# mainboard_mcu_v1_2.net
KiCad netlist of a schematic drawn in Altium Designer
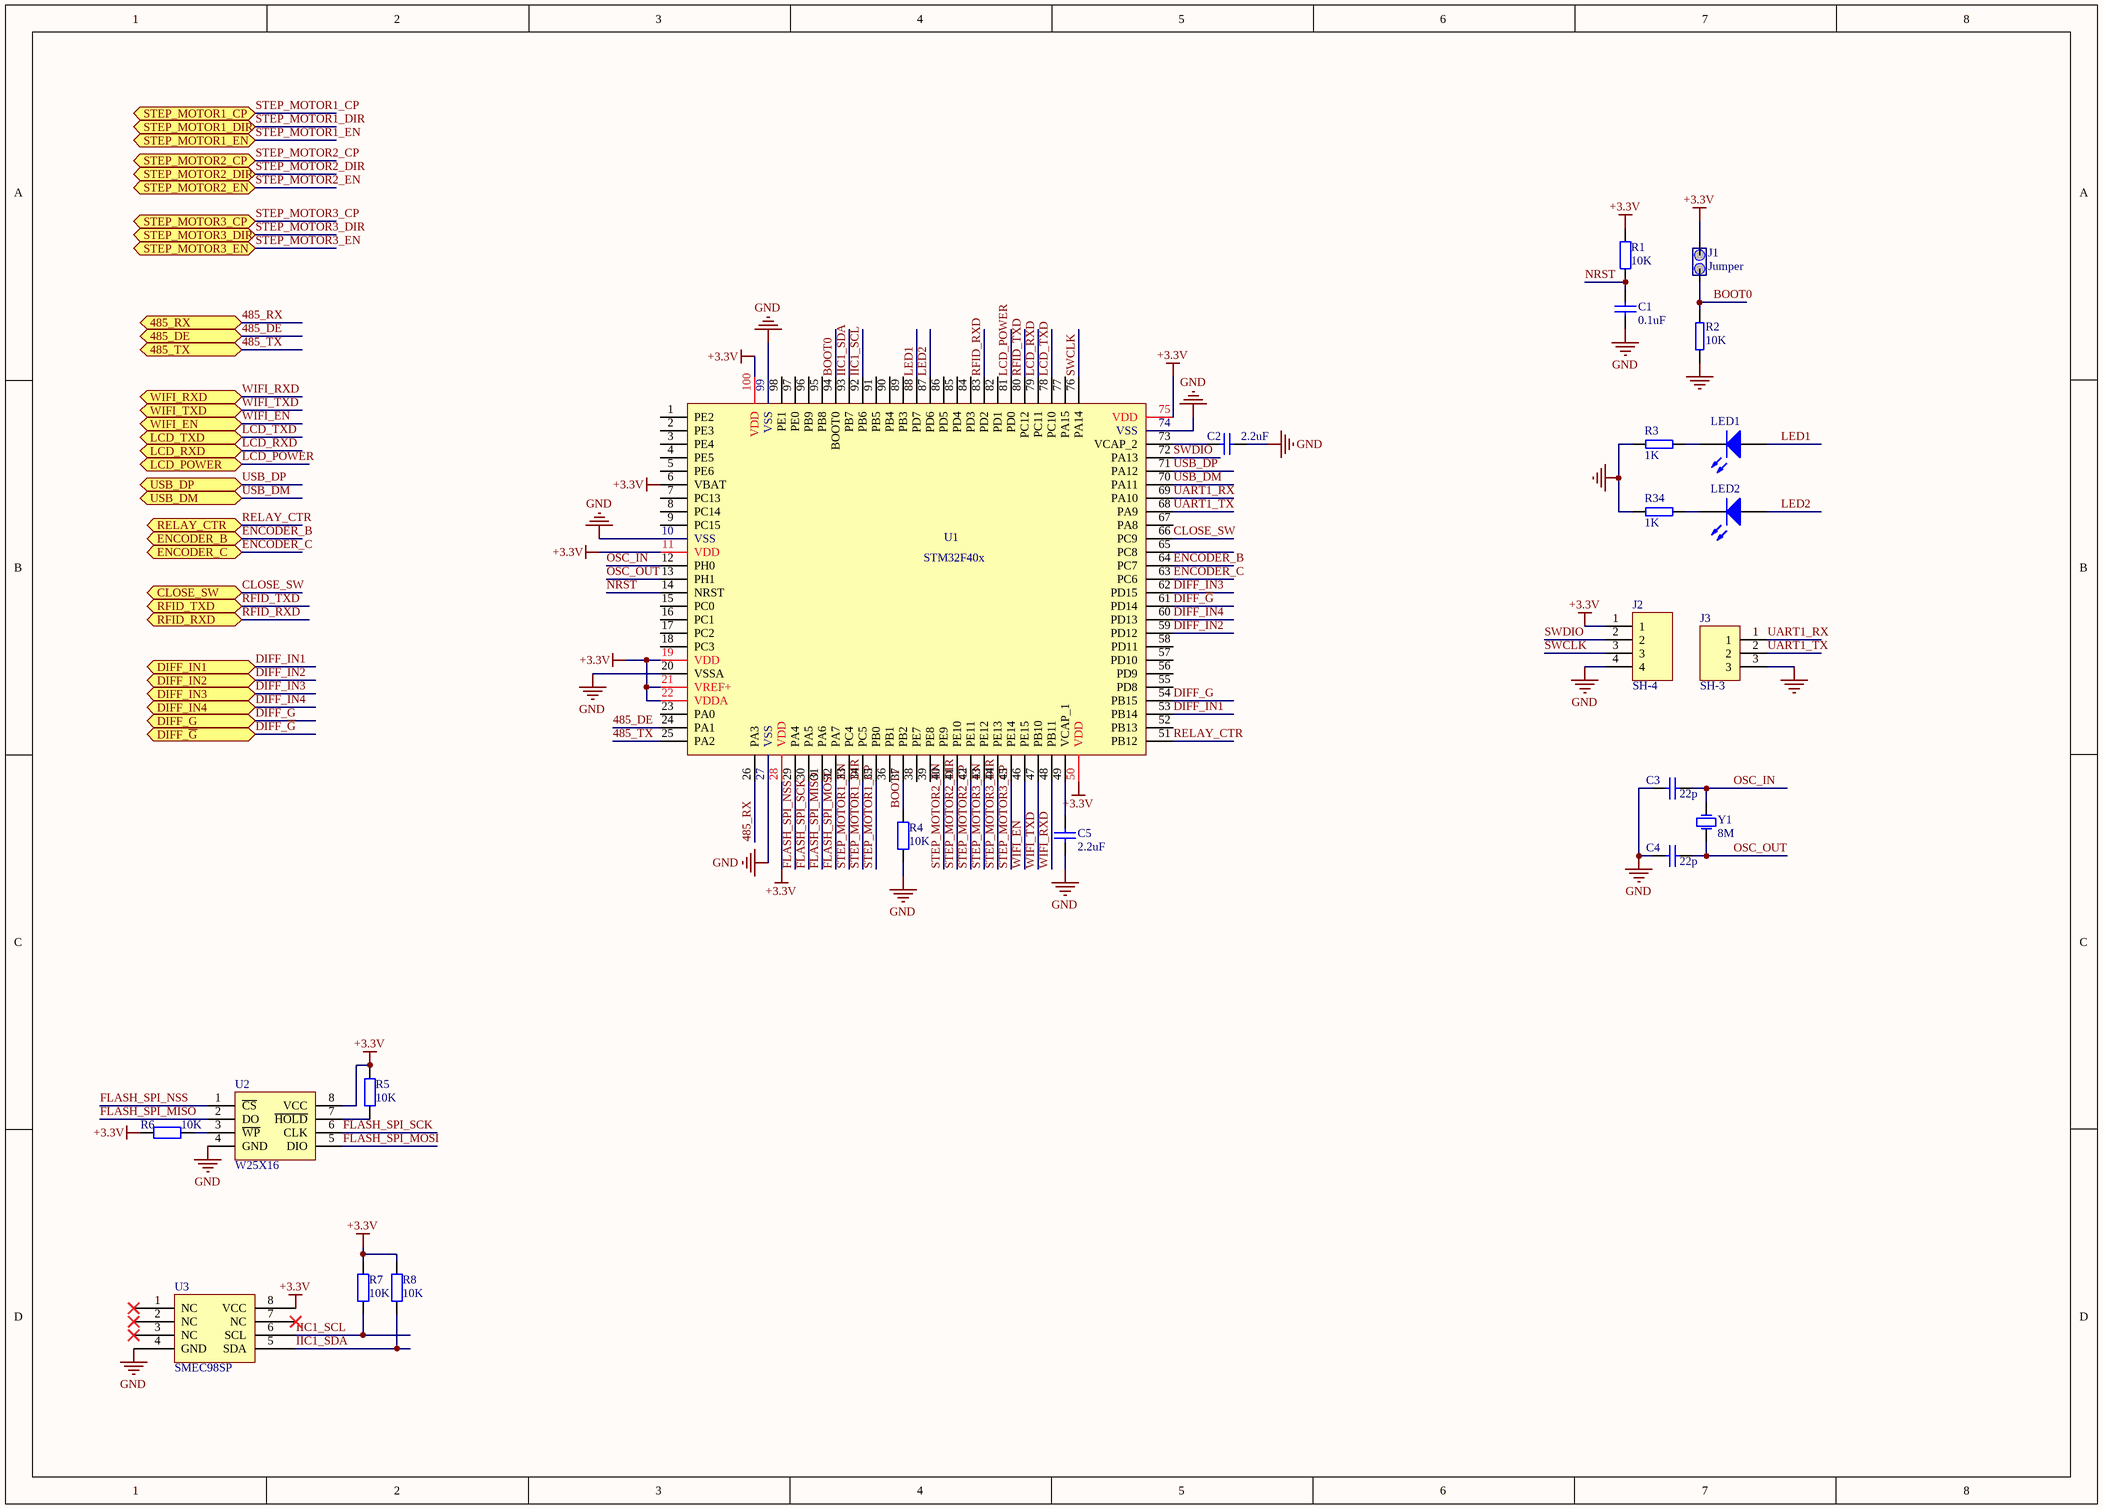
[diagram p0: mainboard_mcu.v1.2.SchDoc]

(export (version "E")
  (design (tool "Eeschema 10.0.6"))
  (components
    (comp (ref "C1")
      (value "0.1uF")
      (footprint "0805")
      (description "Capacitor")
      (fields (field (name "PUBLISHER") "Altium Limited"))
      (libsource (lib "TIAN's Schlib") (part "Cap"))
    )
    (comp (ref "C2")
      (value "2.2uF")
      (footprint "0805")
      (description "Capacitor")
      (fields (field (name "PUBLISHER") "Altium Limited"))
      (libsource (lib "TIAN's Schlib") (part "Cap"))
    )
    (comp (ref "C3")
      (value "22p")
      (footprint "0805")
      (description "Capacitor")
      (fields (field (name "PUBLISHER") "Altium Limited"))
      (libsource (lib "TIAN's Schlib") (part "Cap"))
    )
    (comp (ref "C4")
      (value "22p")
      (footprint "0805")
      (description "Capacitor")
      (fields (field (name "PUBLISHER") "Altium Limited"))
      (libsource (lib "TIAN's Schlib") (part "Cap"))
    )
    (comp (ref "C5")
      (value "2.2uF")
      (footprint "0805")
      (description "Capacitor")
      (fields (field (name "PUBLISHER") "Altium Limited"))
      (libsource (lib "TIAN's Schlib") (part "Cap"))
    )
    (comp (ref "J1") (value "Jumper") (footprint "J254-2") (libsource (lib "Connector") (part "Jumper")))
    (comp (ref "J2") (value "SH-4") (footprint "J254-4") (libsource (lib "Connector") (part "SH-4")))
    (comp (ref "J3") (value "SH-3") (footprint "J2.54-3") (libsource (lib "Connector") (part "SH-3")))
    (comp (ref "LED1")
      (value "GREEN")
      (footprint "LED")
      (description "Typical RED, GREEN, YELLOW, AMBER GaAs LED")
      (fields (field (name "PUBLISHER") "Altium Limited"))
      (libsource (lib "Miscellaneous Devices") (part "LED2"))
    )
    (comp (ref "LED2")
      (value "GREEN")
      (footprint "LED")
      (description "Typical RED, GREEN, YELLOW, AMBER GaAs LED")
      (fields (field (name "PUBLISHER") "Altium Limited"))
      (libsource (lib "Miscellaneous Devices") (part "LED2"))
    )
    (comp (ref "R1")
      (value "10K")
      (footprint "0805")
      (description "Resistor")
      (fields (field (name "PUBLISHER") "Altium Limited"))
      (libsource (lib "") (part "Res2_1"))
    )
    (comp (ref "R2")
      (value "10K")
      (footprint "0805")
      (description "电阻")
      (libsource (lib "Component") (part "RES"))
    )
    (comp (ref "R3")
      (value "1K")
      (footprint "0805")
      (description "电阻")
      (libsource (lib "Component") (part "RES"))
    )
    (comp (ref "R4")
      (value "10K")
      (footprint "0805")
      (description "Resistor")
      (fields (field (name "PUBLISHER") "Altium Limited"))
      (libsource (lib "TIAN's Schlib") (part "Res2"))
    )
    (comp (ref "R5")
      (value "10K")
      (footprint "0805")
      (description "Resistor")
      (fields (field (name "PUBLISHER") "Altium Limited"))
      (libsource (lib "TIAN's Schlib") (part "Res2"))
    )
    (comp (ref "R6")
      (value "10K")
      (footprint "0805")
      (description "Resistor")
      (fields (field (name "PUBLISHER") "Altium Limited"))
      (libsource (lib "") (part "Res2_2"))
    )
    (comp (ref "R7")
      (value "10K")
      (footprint "0805")
      (description "Resistor")
      (fields (field (name "PUBLISHER") "Altium Limited"))
      (libsource (lib "") (part "Res2_1"))
    )
    (comp (ref "R8")
      (value "10K")
      (footprint "0805")
      (description "Resistor")
      (fields (field (name "PUBLISHER") "Altium Limited"))
      (libsource (lib "") (part "Res2_1"))
    )
    (comp (ref "R34")
      (value "1K")
      (footprint "0805")
      (description "电阻")
      (libsource (lib "Component") (part "RES"))
    )
    (comp (ref "U1") (value "STM32F40x") (footprint "TQFP100") (libsource (lib "Chip") (part "STM32F40x")))
    (comp (ref "U2") (value "W25X16") (footprint "SOP8") (libsource (lib "Chip") (part "W25X16")))
    (comp (ref "U3") (value "SMEC98SP") (footprint "SO-8") (libsource (lib "Chip") (part "SMEC98SP")))
    (comp (ref "Y1")
      (value "8M")
      (footprint "XTAL")
      (description "Crystal Oscillator")
      (fields (field (name "PUBLISHER") "Altium Limited"))
      (libsource (lib "TIAN's Schlib") (part "X-32.768"))
    )
  )
  (nets
    (net (code "1") (name "+3.3V") (class "Default")
      (node (ref "J1") (pin "2") (pinfunction "2_2") (pintype "passive"))
      (node (ref "J2") (pin "1") (pinfunction "1_1") (pintype "passive"))
      (node (ref "R1") (pin "2") (pinfunction "2_2") (pintype "passive"))
      (node (ref "R5") (pin "1") (pinfunction "1_1") (pintype "passive"))
      (node (ref "R6") (pin "2") (pinfunction "2_2") (pintype "passive"))
      (node (ref "R7") (pin "2") (pinfunction "2_2") (pintype "passive"))
      (node (ref "R8") (pin "2") (pinfunction "2_2") (pintype "passive"))
      (node (ref "U1") (pin "100") (pinfunction "VDD_100") (pintype "passive"))
      (node (ref "U1") (pin "11") (pinfunction "VDD_11") (pintype "passive"))
      (node (ref "U1") (pin "19") (pinfunction "VDD_19") (pintype "passive"))
      (node (ref "U1") (pin "21") (pinfunction "VREF+_21") (pintype "passive"))
      (node (ref "U1") (pin "22") (pinfunction "VDDA_22") (pintype "passive"))
      (node (ref "U1") (pin "28") (pinfunction "VDD_28") (pintype "passive"))
      (node (ref "U1") (pin "50") (pinfunction "VDD_50") (pintype "passive"))
      (node (ref "U1") (pin "6") (pinfunction "VBAT_6") (pintype "passive"))
      (node (ref "U1") (pin "75") (pinfunction "VDD_75") (pintype "passive"))
      (node (ref "U2") (pin "8") (pinfunction "VCC_8") (pintype "passive"))
      (node (ref "U3") (pin "8") (pinfunction "VCC_8") (pintype "passive"))
    )
    (net (code "2") (name "/485_DE") (class "Default")
      (node (ref "U1") (pin "24") (pinfunction "PA1_24") (pintype "passive"))
    )
    (net (code "3") (name "/485_RX") (class "Default")
      (node (ref "U1") (pin "26") (pinfunction "PA3_26") (pintype "passive"))
    )
    (net (code "4") (name "/485_TX") (class "Default")
      (node (ref "U1") (pin "25") (pinfunction "PA2_25") (pintype "passive"))
    )
    (net (code "5") (name "/BOOT0") (class "Default")
      (node (ref "J1") (pin "1") (pinfunction "1_1") (pintype "passive"))
      (node (ref "R2") (pin "1") (pinfunction "1_1") (pintype "passive"))
      (node (ref "U1") (pin "94") (pinfunction "BOOT0_94") (pintype "passive"))
    )
    (net (code "6") (name "/BOOT1") (class "Default")
      (node (ref "R4") (pin "1") (pinfunction "1_1") (pintype "passive"))
      (node (ref "U1") (pin "37") (pinfunction "PB2_37") (pintype "passive"))
    )
    (net (code "7") (name "/CLOSE_SW") (class "Default")
      (node (ref "U1") (pin "66") (pinfunction "PC9_66") (pintype "passive"))
    )
    (net (code "8") (name "/DIFF_G") (class "Default")
      (node (ref "U1") (pin "54") (pinfunction "PB15_54") (pintype "passive"))
    )
    (net (code "9") (name "/DIFF_IN1") (class "Default")
      (node (ref "U1") (pin "53") (pinfunction "PB14_53") (pintype "passive"))
    )
    (net (code "10") (name "/DIFF_IN2") (class "Default")
      (node (ref "U1") (pin "59") (pinfunction "PD12_59") (pintype "passive"))
    )
    (net (code "11") (name "/DIFF_IN3") (class "Default")
      (node (ref "U1") (pin "62") (pinfunction "PD15_62") (pintype "passive"))
    )
    (net (code "12") (name "/DIFF_IN4") (class "Default")
      (node (ref "U1") (pin "60") (pinfunction "PD13_60") (pintype "passive"))
    )
    (net (code "13") (name "/DIFF_~{G}") (class "Default")
      (node (ref "U1") (pin "61") (pinfunction "PD14_61") (pintype "passive"))
    )
    (net (code "14") (name "/ENCODER_B") (class "Default")
      (node (ref "U1") (pin "64") (pinfunction "PC7_64") (pintype "passive"))
    )
    (net (code "15") (name "/ENCODER_C") (class "Default")
      (node (ref "U1") (pin "63") (pinfunction "PC6_63") (pintype "passive"))
    )
    (net (code "16") (name "/FLASH_SPI_MISO") (class "Default")
      (node (ref "U1") (pin "31") (pinfunction "PA6_31") (pintype "passive"))
      (node (ref "U2") (pin "2") (pinfunction "DO_2") (pintype "passive"))
    )
    (net (code "17") (name "/FLASH_SPI_MOSI") (class "Default")
      (node (ref "U1") (pin "32") (pinfunction "PA7_32") (pintype "passive"))
      (node (ref "U2") (pin "5") (pinfunction "DIO_5") (pintype "passive"))
    )
    (net (code "18") (name "/FLASH_SPI_NSS") (class "Default")
      (node (ref "U1") (pin "29") (pinfunction "PA4_29") (pintype "passive"))
      (node (ref "U2") (pin "1") (pinfunction "~{CS}_1") (pintype "passive"))
    )
    (net (code "19") (name "/FLASH_SPI_SCK") (class "Default")
      (node (ref "U1") (pin "30") (pinfunction "PA5_30") (pintype "passive"))
      (node (ref "U2") (pin "6") (pinfunction "CLK_6") (pintype "passive"))
    )
    (net (code "20") (name "/IIC1_SCL") (class "Default")
      (node (ref "R7") (pin "1") (pinfunction "1_1") (pintype "passive"))
      (node (ref "U1") (pin "92") (pinfunction "PB6_92") (pintype "passive"))
      (node (ref "U3") (pin "6") (pinfunction "SCL_6") (pintype "passive"))
    )
    (net (code "21") (name "/IIC1_SDA") (class "Default")
      (node (ref "R8") (pin "1") (pinfunction "1_1") (pintype "passive"))
      (node (ref "U1") (pin "93") (pinfunction "PB7_93") (pintype "passive"))
      (node (ref "U3") (pin "5") (pinfunction "SDA_5") (pintype "passive"))
    )
    (net (code "22") (name "/LCD_POWER") (class "Default")
      (node (ref "U1") (pin "81") (pinfunction "PD0_81") (pintype "passive"))
    )
    (net (code "23") (name "/LCD_RXD") (class "Default")
      (node (ref "U1") (pin "79") (pinfunction "PC11_79") (pintype "passive"))
    )
    (net (code "24") (name "/LCD_TXD") (class "Default")
      (node (ref "U1") (pin "78") (pinfunction "PC10_78") (pintype "passive"))
    )
    (net (code "25") (name "/LED1") (class "Default")
      (node (ref "LED1") (pin "1") (pinfunction "A_1") (pintype "passive"))
      (node (ref "U1") (pin "88") (pinfunction "PD7_88") (pintype "passive"))
    )
    (net (code "26") (name "/LED2") (class "Default")
      (node (ref "LED2") (pin "1") (pinfunction "A_1") (pintype "passive"))
      (node (ref "U1") (pin "87") (pinfunction "PD6_87") (pintype "passive"))
    )
    (net (code "27") (name "/NRST") (class "Default")
      (node (ref "C1") (pin "2") (pinfunction "2_2") (pintype "passive"))
      (node (ref "R1") (pin "1") (pinfunction "1_1") (pintype "passive"))
      (node (ref "U1") (pin "14") (pinfunction "NRST_14") (pintype "passive"))
    )
    (net (code "28") (name "/OSC_IN") (class "Default")
      (node (ref "C3") (pin "1") (pinfunction "1_1") (pintype "passive"))
      (node (ref "U1") (pin "12") (pinfunction "PH0_12") (pintype "passive"))
      (node (ref "Y1") (pin "2") (pinfunction "OSC2_2") (pintype "passive"))
    )
    (net (code "29") (name "/OSC_OUT") (class "Default")
      (node (ref "C4") (pin "1") (pinfunction "1_1") (pintype "passive"))
      (node (ref "U1") (pin "13") (pinfunction "PH1_13") (pintype "passive"))
      (node (ref "Y1") (pin "1") (pinfunction "OSC1_1") (pintype "passive"))
    )
    (net (code "30") (name "/RELAY_CTR") (class "Default")
      (node (ref "U1") (pin "51") (pinfunction "PB12_51") (pintype "passive"))
    )
    (net (code "31") (name "/RFID_RXD") (class "Default")
      (node (ref "U1") (pin "83") (pinfunction "PD2_83") (pintype "passive"))
    )
    (net (code "32") (name "/RFID_TXD") (class "Default")
      (node (ref "U1") (pin "80") (pinfunction "PC12_80") (pintype "passive"))
    )
    (net (code "33") (name "/STEP_MOTOR1_CP") (class "Default")
      (node (ref "U1") (pin "35") (pinfunction "PB0_35") (pintype "passive"))
    )
    (net (code "34") (name "/STEP_MOTOR1_DIR") (class "Default")
      (node (ref "U1") (pin "34") (pinfunction "PC5_34") (pintype "passive"))
    )
    (net (code "35") (name "/STEP_MOTOR1_EN") (class "Default")
      (node (ref "U1") (pin "33") (pinfunction "PC4_33") (pintype "passive"))
    )
    (net (code "36") (name "/STEP_MOTOR2_CP") (class "Default")
      (node (ref "U1") (pin "42") (pinfunction "PE11_42") (pintype "passive"))
    )
    (net (code "37") (name "/STEP_MOTOR2_DIR") (class "Default")
      (node (ref "U1") (pin "41") (pinfunction "PE10_41") (pintype "passive"))
    )
    (net (code "38") (name "/STEP_MOTOR2_EN") (class "Default")
      (node (ref "U1") (pin "40") (pinfunction "PE9_40") (pintype "passive"))
    )
    (net (code "39") (name "/STEP_MOTOR3_CP") (class "Default")
      (node (ref "U1") (pin "45") (pinfunction "PE14_45") (pintype "passive"))
    )
    (net (code "40") (name "/STEP_MOTOR3_DIR") (class "Default")
      (node (ref "U1") (pin "44") (pinfunction "PE13_44") (pintype "passive"))
    )
    (net (code "41") (name "/STEP_MOTOR3_EN") (class "Default")
      (node (ref "U1") (pin "43") (pinfunction "PE12_43") (pintype "passive"))
    )
    (net (code "42") (name "/SWCLK") (class "Default")
      (node (ref "J2") (pin "3") (pinfunction "3_3") (pintype "passive"))
      (node (ref "U1") (pin "76") (pinfunction "PA14_76") (pintype "passive"))
    )
    (net (code "43") (name "/SWDIO") (class "Default")
      (node (ref "J2") (pin "2") (pinfunction "2_2") (pintype "passive"))
      (node (ref "U1") (pin "72") (pinfunction "PA13_72") (pintype "passive"))
    )
    (net (code "44") (name "/UART1_RX") (class "Default")
      (node (ref "J3") (pin "1") (pinfunction "1_1") (pintype "passive"))
      (node (ref "U1") (pin "69") (pinfunction "PA10_69") (pintype "passive"))
    )
    (net (code "45") (name "/UART1_TX") (class "Default")
      (node (ref "J3") (pin "2") (pinfunction "2_2") (pintype "passive"))
      (node (ref "U1") (pin "68") (pinfunction "PA9_68") (pintype "passive"))
    )
    (net (code "46") (name "/USB_DM") (class "Default")
      (node (ref "U1") (pin "70") (pinfunction "PA11_70") (pintype "passive"))
    )
    (net (code "47") (name "/USB_DP") (class "Default")
      (node (ref "U1") (pin "71") (pinfunction "PA12_71") (pintype "passive"))
    )
    (net (code "48") (name "/WIFI_EN") (class "Default")
      (node (ref "U1") (pin "46") (pinfunction "PE15_46") (pintype "passive"))
    )
    (net (code "49") (name "/WIFI_RXD") (class "Default")
      (node (ref "U1") (pin "48") (pinfunction "PB11_48") (pintype "passive"))
    )
    (net (code "50") (name "/WIFI_TXD") (class "Default")
      (node (ref "U1") (pin "47") (pinfunction "PB10_47") (pintype "passive"))
    )
    (net (code "51") (name "GND") (class "Default")
      (node (ref "C1") (pin "1") (pinfunction "1_1") (pintype "passive"))
      (node (ref "C2") (pin "1") (pinfunction "1_1") (pintype "passive"))
      (node (ref "C3") (pin "2") (pinfunction "2_2") (pintype "passive"))
      (node (ref "C4") (pin "2") (pinfunction "2_2") (pintype "passive"))
      (node (ref "C5") (pin "2") (pinfunction "2_2") (pintype "passive"))
      (node (ref "J2") (pin "4") (pinfunction "4_4") (pintype "passive"))
      (node (ref "J3") (pin "3") (pinfunction "3_3") (pintype "passive"))
      (node (ref "R2") (pin "2") (pinfunction "2_2") (pintype "passive"))
      (node (ref "R3") (pin "2") (pinfunction "2_2") (pintype "passive"))
      (node (ref "R34") (pin "2") (pinfunction "2_2") (pintype "passive"))
      (node (ref "R4") (pin "2") (pinfunction "2_2") (pintype "passive"))
      (node (ref "U1") (pin "10") (pinfunction "VSS_10") (pintype "passive"))
      (node (ref "U1") (pin "20") (pinfunction "VSSA_20") (pintype "passive"))
      (node (ref "U1") (pin "27") (pinfunction "VSS_27") (pintype "passive"))
      (node (ref "U1") (pin "74") (pinfunction "VSS_74") (pintype "passive"))
      (node (ref "U1") (pin "99") (pinfunction "VSS_99") (pintype "passive"))
      (node (ref "U2") (pin "4") (pinfunction "GND_4") (pintype "passive"))
      (node (ref "U3") (pin "4") (pinfunction "GND_4") (pintype "passive"))
    )
    (net (code "52") (name "Net-(LED1-K)") (class "Default")
      (node (ref "LED1") (pin "2") (pinfunction "K_2") (pintype "passive"))
      (node (ref "R3") (pin "1") (pinfunction "1_1") (pintype "passive"))
    )
    (net (code "53") (name "Net-(LED2-K)") (class "Default")
      (node (ref "LED2") (pin "2") (pinfunction "K_2") (pintype "passive"))
      (node (ref "R34") (pin "1") (pinfunction "1_1") (pintype "passive"))
    )
    (net (code "54") (name "Net-(U1-VCAP_1)") (class "Default")
      (node (ref "C5") (pin "1") (pinfunction "1_1") (pintype "passive"))
      (node (ref "U1") (pin "49") (pinfunction "VCAP_1_49") (pintype "passive"))
    )
    (net (code "55") (name "Net-(U1-VCAP_2)") (class "Default")
      (node (ref "C2") (pin "2") (pinfunction "2_2") (pintype "passive"))
      (node (ref "U1") (pin "73") (pinfunction "VCAP_2_73") (pintype "passive"))
    )
    (net (code "56") (name "Net-(U2-~{HOLD})") (class "Default")
      (node (ref "R5") (pin "2") (pinfunction "2_2") (pintype "passive"))
      (node (ref "U2") (pin "7") (pinfunction "~{HOLD}_7") (pintype "passive"))
    )
    (net (code "57") (name "Net-(U2-~{WP})") (class "Default")
      (node (ref "R6") (pin "1") (pinfunction "1_1") (pintype "passive"))
      (node (ref "U2") (pin "3") (pinfunction "~{WP}_3") (pintype "passive"))
    )
    (net (code "58") (name "unconnected-(U1-PA0-Pad23)") (class "Default")
      (node (ref "U1") (pin "23") (pinfunction "PA0_23") (pintype "passive"))
    )
    (net (code "59") (name "unconnected-(U1-PA8-Pad67)") (class "Default")
      (node (ref "U1") (pin "67") (pinfunction "PA8_67") (pintype "passive"))
    )
    (net (code "60") (name "unconnected-(U1-PA15-Pad77)") (class "Default")
      (node (ref "U1") (pin "77") (pinfunction "PA15_77") (pintype "passive"))
    )
    (net (code "61") (name "unconnected-(U1-PB1-Pad36)") (class "Default")
      (node (ref "U1") (pin "36") (pinfunction "PB1_36") (pintype "passive"))
    )
    (net (code "62") (name "unconnected-(U1-PB3-Pad89)") (class "Default")
      (node (ref "U1") (pin "89") (pinfunction "PB3_89") (pintype "passive"))
    )
    (net (code "63") (name "unconnected-(U1-PB4-Pad90)") (class "Default")
      (node (ref "U1") (pin "90") (pinfunction "PB4_90") (pintype "passive"))
    )
    (net (code "64") (name "unconnected-(U1-PB5-Pad91)") (class "Default")
      (node (ref "U1") (pin "91") (pinfunction "PB5_91") (pintype "passive"))
    )
    (net (code "65") (name "unconnected-(U1-PB8-Pad95)") (class "Default")
      (node (ref "U1") (pin "95") (pinfunction "PB8_95") (pintype "passive"))
    )
    (net (code "66") (name "unconnected-(U1-PB9-Pad96)") (class "Default")
      (node (ref "U1") (pin "96") (pinfunction "PB9_96") (pintype "passive"))
    )
    (net (code "67") (name "unconnected-(U1-PB13-Pad52)") (class "Default")
      (node (ref "U1") (pin "52") (pinfunction "PB13_52") (pintype "passive"))
    )
    (net (code "68") (name "unconnected-(U1-PC0-Pad15)") (class "Default")
      (node (ref "U1") (pin "15") (pinfunction "PC0_15") (pintype "passive"))
    )
    (net (code "69") (name "unconnected-(U1-PC1-Pad16)") (class "Default")
      (node (ref "U1") (pin "16") (pinfunction "PC1_16") (pintype "passive"))
    )
    (net (code "70") (name "unconnected-(U1-PC2-Pad17)") (class "Default")
      (node (ref "U1") (pin "17") (pinfunction "PC2_17") (pintype "passive"))
    )
    (net (code "71") (name "unconnected-(U1-PC3-Pad18)") (class "Default")
      (node (ref "U1") (pin "18") (pinfunction "PC3_18") (pintype "passive"))
    )
    (net (code "72") (name "unconnected-(U1-PC8-Pad65)") (class "Default")
      (node (ref "U1") (pin "65") (pinfunction "PC8_65") (pintype "passive"))
    )
    (net (code "73") (name "unconnected-(U1-PC13-Pad7)") (class "Default")
      (node (ref "U1") (pin "7") (pinfunction "PC13_7") (pintype "passive"))
    )
    (net (code "74") (name "unconnected-(U1-PC14-Pad8)") (class "Default")
      (node (ref "U1") (pin "8") (pinfunction "PC14_8") (pintype "passive"))
    )
    (net (code "75") (name "unconnected-(U1-PC15-Pad9)") (class "Default")
      (node (ref "U1") (pin "9") (pinfunction "PC15_9") (pintype "passive"))
    )
    (net (code "76") (name "unconnected-(U1-PD1-Pad82)") (class "Default")
      (node (ref "U1") (pin "82") (pinfunction "PD1_82") (pintype "passive"))
    )
    (net (code "77") (name "unconnected-(U1-PD3-Pad84)") (class "Default")
      (node (ref "U1") (pin "84") (pinfunction "PD3_84") (pintype "passive"))
    )
    (net (code "78") (name "unconnected-(U1-PD4-Pad85)") (class "Default")
      (node (ref "U1") (pin "85") (pinfunction "PD4_85") (pintype "passive"))
    )
    (net (code "79") (name "unconnected-(U1-PD5-Pad86)") (class "Default")
      (node (ref "U1") (pin "86") (pinfunction "PD5_86") (pintype "passive"))
    )
    (net (code "80") (name "unconnected-(U1-PD8-Pad55)") (class "Default")
      (node (ref "U1") (pin "55") (pinfunction "PD8_55") (pintype "passive"))
    )
    (net (code "81") (name "unconnected-(U1-PD9-Pad56)") (class "Default")
      (node (ref "U1") (pin "56") (pinfunction "PD9_56") (pintype "passive"))
    )
    (net (code "82") (name "unconnected-(U1-PD10-Pad57)") (class "Default")
      (node (ref "U1") (pin "57") (pinfunction "PD10_57") (pintype "passive"))
    )
    (net (code "83") (name "unconnected-(U1-PD11-Pad58)") (class "Default")
      (node (ref "U1") (pin "58") (pinfunction "PD11_58") (pintype "passive"))
    )
    (net (code "84") (name "unconnected-(U1-PE0-Pad97)") (class "Default")
      (node (ref "U1") (pin "97") (pinfunction "PE0_97") (pintype "passive"))
    )
    (net (code "85") (name "unconnected-(U1-PE1-Pad98)") (class "Default")
      (node (ref "U1") (pin "98") (pinfunction "PE1_98") (pintype "passive"))
    )
    (net (code "86") (name "unconnected-(U1-PE2-Pad1)") (class "Default")
      (node (ref "U1") (pin "1") (pinfunction "PE2_1") (pintype "passive"))
    )
    (net (code "87") (name "unconnected-(U1-PE3-Pad2)") (class "Default")
      (node (ref "U1") (pin "2") (pinfunction "PE3_2") (pintype "passive"))
    )
    (net (code "88") (name "unconnected-(U1-PE4-Pad3)") (class "Default")
      (node (ref "U1") (pin "3") (pinfunction "PE4_3") (pintype "passive"))
    )
    (net (code "89") (name "unconnected-(U1-PE5-Pad4)") (class "Default")
      (node (ref "U1") (pin "4") (pinfunction "PE5_4") (pintype "passive"))
    )
    (net (code "90") (name "unconnected-(U1-PE6-Pad5)") (class "Default")
      (node (ref "U1") (pin "5") (pinfunction "PE6_5") (pintype "passive"))
    )
    (net (code "91") (name "unconnected-(U1-PE7-Pad38)") (class "Default")
      (node (ref "U1") (pin "38") (pinfunction "PE7_38") (pintype "passive"))
    )
    (net (code "92") (name "unconnected-(U1-PE8-Pad39)") (class "Default")
      (node (ref "U1") (pin "39") (pinfunction "PE8_39") (pintype "passive"))
    )
    (net (code "93") (name "unconnected-(U3-NC-Pad1)") (class "Default")
      (node (ref "U3") (pin "1") (pinfunction "NC_1") (pintype "passive+no_connect"))
    )
    (net (code "94") (name "unconnected-(U3-NC-Pad2)") (class "Default")
      (node (ref "U3") (pin "2") (pinfunction "NC_2") (pintype "passive+no_connect"))
    )
    (net (code "95") (name "unconnected-(U3-NC-Pad3)") (class "Default")
      (node (ref "U3") (pin "3") (pinfunction "NC_3") (pintype "passive+no_connect"))
    )
    (net (code "96") (name "unconnected-(U3-NC-Pad7)") (class "Default")
      (node (ref "U3") (pin "7") (pinfunction "NC_7") (pintype "passive+no_connect"))
    )
  )
)
